# LCDTFT_FPC50P_RGB.net
KiCad netlist of a schematic drawn in Altium Designer
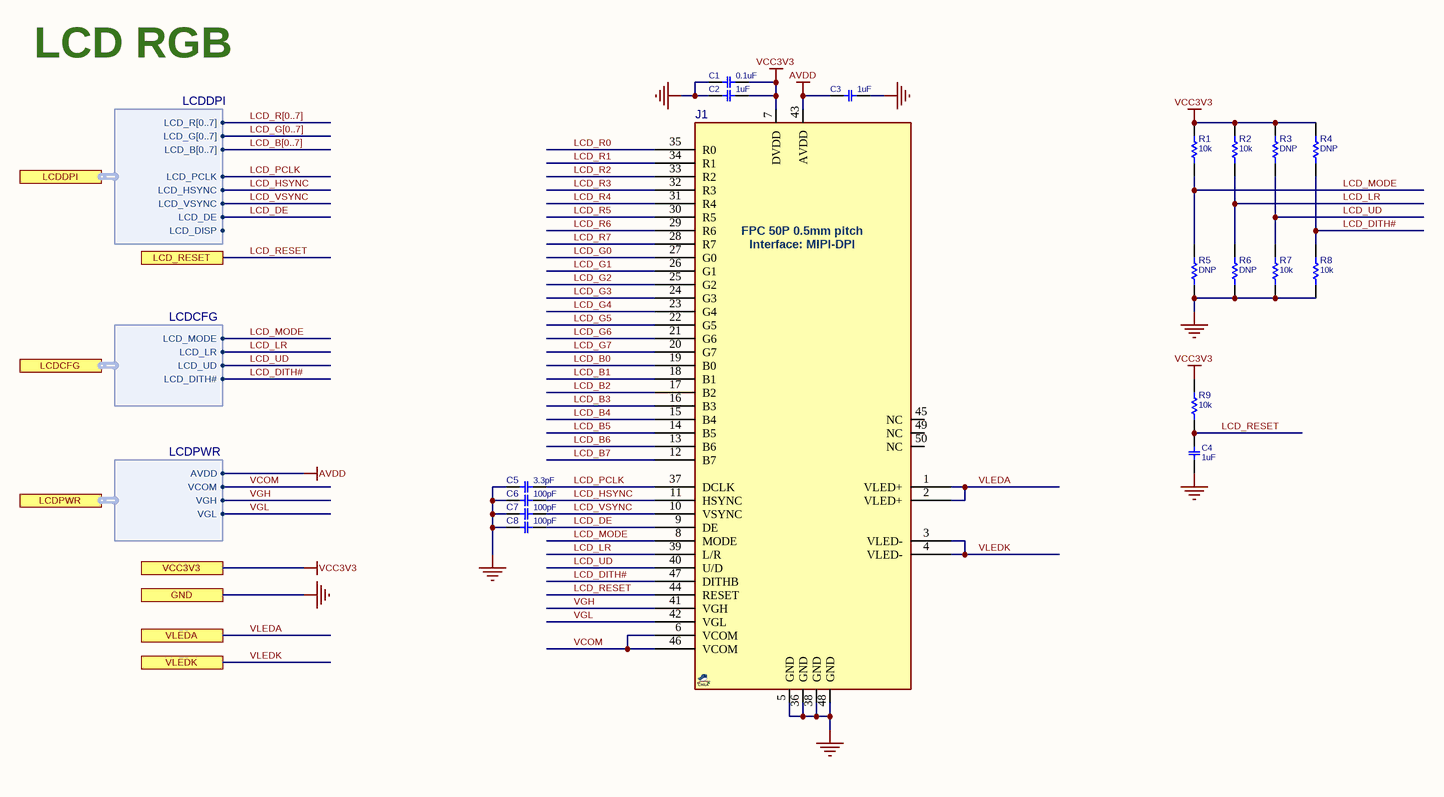
[diagram p0: LCDTFT_FPC50P_RGB.SchDoc]

(export (version "E")
  (design (tool "Eeschema 10.0.6"))
  (components
    (comp (ref "C1")
      (value "0.1uF")
      (footprint "C0402")
      (description "CAP, MLCC")
      (fields (field (name "MANF_P#") "GRM155R71H104KE14D") (field (name "MANF") "Murata"))
      (libsource (lib "passive_smd") (part "CAP_SMD_MLCC"))
    )
    (comp (ref "C2")
      (value "1uF")
      (footprint "C0402")
      (description "CAP, MLCC")
      (fields (field (name "MANF_P#") "CL05A105KO5NNND") (field (name "MANF") "Samsung"))
      (libsource (lib "passive_smd") (part "CAP_SMD_MLCC"))
    )
    (comp (ref "C3")
      (value "1uF")
      (footprint "C0402")
      (description "CAP, MLCC")
      (fields (field (name "MANF_P#") "CL05A105KO5NNND") (field (name "MANF") "Samsung"))
      (libsource (lib "passive_smd") (part "CAP_SMD_MLCC"))
    )
    (comp (ref "C4")
      (value "1uF")
      (footprint "C0402")
      (description "CAP, MLCC")
      (fields (field (name "MANF_P#") "CL05A105KO5NNND") (field (name "MANF") "Samsung"))
      (libsource (lib "passive_smd") (part "CAP_SMD_MLCC"))
    )
    (comp (ref "C5")
      (value "3.3pF")
      (footprint "C0402")
      (description "CAP, MLCC")
      (libsource (lib "passive_smd") (part "CAP_SMD_MLCC"))
    )
    (comp (ref "C6")
      (value "100pF")
      (footprint "C0402")
      (description "CAP, MLCC")
      (libsource (lib "passive_smd") (part "CAP_SMD_MLCC"))
    )
    (comp (ref "C7")
      (value "100pF")
      (footprint "C0402")
      (description "CAP, MLCC")
      (libsource (lib "passive_smd") (part "CAP_SMD_MLCC"))
    )
    (comp (ref "C8")
      (value "100pF")
      (footprint "C0402")
      (description "CAP, MLCC")
      (libsource (lib "passive_smd") (part "CAP_SMD_MLCC"))
    )
    (comp (ref "J1")
      (value "FPC_50_0.5mm")
      (footprint "FPC50_50D_FFC2B29")
      (description "LCD TFT Color, FPC50P, RGB")
      (libsource (lib "lcdtft") (part "LCDTFT_DPI_FPC50P"))
    )
    (comp (ref "R1")
      (value "10k")
      (footprint "R0402")
      (description "RESISTOR, SMD")
      (libsource (lib "passive_res_smd") (part "RES_SMD"))
    )
    (comp (ref "R2")
      (value "10k")
      (footprint "R0402")
      (description "RESISTOR, SMD")
      (libsource (lib "passive_res_smd") (part "RES_SMD"))
    )
    (comp (ref "R3")
      (value "DNP")
      (footprint "R0402")
      (description "RESISTOR, SMD")
      (libsource (lib "passive_res_smd") (part "RES_SMD"))
    )
    (comp (ref "R4")
      (value "DNP")
      (footprint "R0402")
      (description "RESISTOR, SMD")
      (libsource (lib "passive_res_smd") (part "RES_SMD"))
    )
    (comp (ref "R5")
      (value "DNP")
      (footprint "R0402")
      (description "RESISTOR, SMD")
      (libsource (lib "passive_res_smd") (part "RES_SMD"))
    )
    (comp (ref "R6")
      (value "DNP")
      (footprint "R0402")
      (description "RESISTOR, SMD")
      (libsource (lib "passive_res_smd") (part "RES_SMD"))
    )
    (comp (ref "R7")
      (value "10k")
      (footprint "R0402")
      (description "RESISTOR, SMD")
      (libsource (lib "passive_res_smd") (part "RES_SMD"))
    )
    (comp (ref "R8")
      (value "10k")
      (footprint "R0402")
      (description "RESISTOR, SMD")
      (libsource (lib "passive_res_smd") (part "RES_SMD"))
    )
    (comp (ref "R9")
      (value "10k")
      (footprint "R0402")
      (description "RESISTOR, SMD")
      (libsource (lib "passive_res_smd") (part "RES_SMD"))
    )
  )
  (nets
    (net (code "4") (name "/LCD_B0") (class "Default")
      (node (ref "J1") (pin "19") (pinfunction "B0_19") (pintype "passive"))
    )
    (net (code "5") (name "/LCD_B1") (class "Default")
      (node (ref "J1") (pin "18") (pinfunction "B1_18") (pintype "passive"))
    )
    (net (code "6") (name "/LCD_B2") (class "Default")
      (node (ref "J1") (pin "17") (pinfunction "B2_17") (pintype "passive"))
    )
    (net (code "7") (name "/LCD_B3") (class "Default")
      (node (ref "J1") (pin "16") (pinfunction "B3_16") (pintype "passive"))
    )
    (net (code "8") (name "/LCD_B4") (class "Default")
      (node (ref "J1") (pin "15") (pinfunction "B4_15") (pintype "passive"))
    )
    (net (code "9") (name "/LCD_B5") (class "Default")
      (node (ref "J1") (pin "14") (pinfunction "B5_14") (pintype "passive"))
    )
    (net (code "10") (name "/LCD_B6") (class "Default")
      (node (ref "J1") (pin "13") (pinfunction "B6_13") (pintype "passive"))
    )
    (net (code "11") (name "/LCD_B7") (class "Default")
      (node (ref "J1") (pin "12") (pinfunction "B7_12") (pintype "passive"))
    )
    (net (code "13") (name "/LCD_DE") (class "Default")
      (node (ref "C8") (pin "1") (pinfunction "1_1") (pintype "passive"))
      (node (ref "J1") (pin "9") (pinfunction "DE_9") (pintype "passive"))
    )
    (net (code "14") (name "/LCD_DITH#") (class "Default")
      (node (ref "J1") (pin "47") (pinfunction "DITHB_47") (pintype "passive"))
      (node (ref "R4") (pin "2") (pinfunction "2_2") (pintype "passive"))
      (node (ref "R8") (pin "1") (pinfunction "1_1") (pintype "passive"))
    )
    (net (code "15") (name "/LCD_G0") (class "Default")
      (node (ref "J1") (pin "27") (pinfunction "G0_27") (pintype "passive"))
    )
    (net (code "16") (name "/LCD_G1") (class "Default")
      (node (ref "J1") (pin "26") (pinfunction "G1_26") (pintype "passive"))
    )
    (net (code "17") (name "/LCD_G2") (class "Default")
      (node (ref "J1") (pin "25") (pinfunction "G2_25") (pintype "passive"))
    )
    (net (code "18") (name "/LCD_G3") (class "Default")
      (node (ref "J1") (pin "24") (pinfunction "G3_24") (pintype "passive"))
    )
    (net (code "19") (name "/LCD_G4") (class "Default")
      (node (ref "J1") (pin "23") (pinfunction "G4_23") (pintype "passive"))
    )
    (net (code "20") (name "/LCD_G5") (class "Default")
      (node (ref "J1") (pin "22") (pinfunction "G5_22") (pintype "passive"))
    )
    (net (code "21") (name "/LCD_G6") (class "Default")
      (node (ref "J1") (pin "21") (pinfunction "G6_21") (pintype "passive"))
    )
    (net (code "22") (name "/LCD_G7") (class "Default")
      (node (ref "J1") (pin "20") (pinfunction "G7_20") (pintype "passive"))
    )
    (net (code "24") (name "/LCD_HSYNC") (class "Default")
      (node (ref "C6") (pin "1") (pinfunction "1_1") (pintype "passive"))
      (node (ref "J1") (pin "11") (pinfunction "HSYNC_11") (pintype "passive"))
    )
    (net (code "25") (name "/LCD_LR") (class "Default")
      (node (ref "J1") (pin "39") (pinfunction "L/R_39") (pintype "passive"))
      (node (ref "R2") (pin "2") (pinfunction "2_2") (pintype "passive"))
      (node (ref "R6") (pin "1") (pinfunction "1_1") (pintype "passive"))
    )
    (net (code "26") (name "/LCD_MODE") (class "Default")
      (node (ref "J1") (pin "8") (pinfunction "MODE_8") (pintype "passive"))
      (node (ref "R1") (pin "2") (pinfunction "2_2") (pintype "passive"))
      (node (ref "R5") (pin "1") (pinfunction "1_1") (pintype "passive"))
    )
    (net (code "27") (name "/LCD_PCLK") (class "Default")
      (node (ref "C5") (pin "1") (pinfunction "1_1") (pintype "passive"))
      (node (ref "J1") (pin "37") (pinfunction "DCLK_37") (pintype "passive"))
    )
    (net (code "28") (name "/LCD_R0") (class "Default")
      (node (ref "J1") (pin "35") (pinfunction "R0_35") (pintype "passive"))
    )
    (net (code "29") (name "/LCD_R1") (class "Default")
      (node (ref "J1") (pin "34") (pinfunction "R1_34") (pintype "passive"))
    )
    (net (code "30") (name "/LCD_R2") (class "Default")
      (node (ref "J1") (pin "33") (pinfunction "R2_33") (pintype "passive"))
    )
    (net (code "31") (name "/LCD_R3") (class "Default")
      (node (ref "J1") (pin "32") (pinfunction "R3_32") (pintype "passive"))
    )
    (net (code "32") (name "/LCD_R4") (class "Default")
      (node (ref "J1") (pin "31") (pinfunction "R4_31") (pintype "passive"))
    )
    (net (code "33") (name "/LCD_R5") (class "Default")
      (node (ref "J1") (pin "30") (pinfunction "R5_30") (pintype "passive"))
    )
    (net (code "34") (name "/LCD_R6") (class "Default")
      (node (ref "J1") (pin "29") (pinfunction "R6_29") (pintype "passive"))
    )
    (net (code "35") (name "/LCD_R7") (class "Default")
      (node (ref "J1") (pin "28") (pinfunction "R7_28") (pintype "passive"))
    )
    (net (code "36") (name "/LCD_RESET") (class "Default")
      (node (ref "C4") (pin "1") (pinfunction "1_1") (pintype "passive"))
      (node (ref "J1") (pin "44") (pinfunction "RESET_44") (pintype "passive"))
      (node (ref "R9") (pin "2") (pinfunction "2_2") (pintype "passive"))
    )
    (net (code "38") (name "/LCD_UD") (class "Default")
      (node (ref "J1") (pin "40") (pinfunction "U/D_40") (pintype "passive"))
      (node (ref "R3") (pin "2") (pinfunction "2_2") (pintype "passive"))
      (node (ref "R7") (pin "1") (pinfunction "1_1") (pintype "passive"))
    )
    (net (code "39") (name "/LCD_VSYNC") (class "Default")
      (node (ref "C7") (pin "1") (pinfunction "1_1") (pintype "passive"))
      (node (ref "J1") (pin "10") (pinfunction "VSYNC_10") (pintype "passive"))
    )
    (net (code "40") (name "/VCOM") (class "Default")
      (node (ref "J1") (pin "46") (pinfunction "VCOM_46") (pintype "passive"))
      (node (ref "J1") (pin "6") (pinfunction "VCOM_6") (pintype "passive"))
    )
    (net (code "41") (name "/VGH") (class "Default")
      (node (ref "J1") (pin "41") (pinfunction "VGH_41") (pintype "passive"))
    )
    (net (code "42") (name "/VGL") (class "Default")
      (node (ref "J1") (pin "42") (pinfunction "VGL_42") (pintype "passive"))
    )
    (net (code "43") (name "/VLEDA") (class "Default")
      (node (ref "J1") (pin "1") (pinfunction "VLED+_1") (pintype "passive"))
      (node (ref "J1") (pin "2") (pinfunction "VLED+_2") (pintype "passive"))
    )
    (net (code "44") (name "/VLEDK") (class "Default")
      (node (ref "J1") (pin "3") (pinfunction "VLED-_3") (pintype "passive"))
      (node (ref "J1") (pin "4") (pinfunction "VLED-_4") (pintype "passive"))
    )
    (net (code "48") (name "AVDD") (class "Default")
      (node (ref "C3") (pin "2") (pinfunction "2_2") (pintype "passive"))
      (node (ref "J1") (pin "43") (pinfunction "AVDD_43") (pintype "passive"))
    )
    (net (code "49") (name "GND") (class "Default")
      (node (ref "C1") (pin "2") (pinfunction "2_2") (pintype "passive"))
      (node (ref "C2") (pin "2") (pinfunction "2_2") (pintype "passive"))
      (node (ref "C3") (pin "1") (pinfunction "1_1") (pintype "passive"))
      (node (ref "C4") (pin "2") (pinfunction "2_2") (pintype "passive"))
      (node (ref "C5") (pin "2") (pinfunction "2_2") (pintype "passive"))
      (node (ref "C6") (pin "2") (pinfunction "2_2") (pintype "passive"))
      (node (ref "C7") (pin "2") (pinfunction "2_2") (pintype "passive"))
      (node (ref "C8") (pin "2") (pinfunction "2_2") (pintype "passive"))
      (node (ref "J1") (pin "36") (pinfunction "GND_36") (pintype "passive"))
      (node (ref "J1") (pin "38") (pinfunction "GND_38") (pintype "passive"))
      (node (ref "J1") (pin "48") (pinfunction "GND_48") (pintype "passive"))
      (node (ref "J1") (pin "5") (pinfunction "GND_5") (pintype "passive"))
      (node (ref "R5") (pin "2") (pinfunction "2_2") (pintype "passive"))
      (node (ref "R6") (pin "2") (pinfunction "2_2") (pintype "passive"))
      (node (ref "R7") (pin "2") (pinfunction "2_2") (pintype "passive"))
      (node (ref "R8") (pin "2") (pinfunction "2_2") (pintype "passive"))
    )
    (net (code "50") (name "VCC3V3") (class "Default")
      (node (ref "C1") (pin "1") (pinfunction "1_1") (pintype "passive"))
      (node (ref "C2") (pin "1") (pinfunction "1_1") (pintype "passive"))
      (node (ref "J1") (pin "7") (pinfunction "DVDD_7") (pintype "passive"))
      (node (ref "R1") (pin "1") (pinfunction "1_1") (pintype "passive"))
      (node (ref "R2") (pin "1") (pinfunction "1_1") (pintype "passive"))
      (node (ref "R3") (pin "1") (pinfunction "1_1") (pintype "passive"))
      (node (ref "R4") (pin "1") (pinfunction "1_1") (pintype "passive"))
      (node (ref "R9") (pin "1") (pinfunction "1_1") (pintype "passive"))
    )
    (net (code "51") (name "unconnected-(J1-NC-Pad45)") (class "Default")
      (node (ref "J1") (pin "45") (pinfunction "NC_45") (pintype "passive"))
    )
    (net (code "52") (name "unconnected-(J1-NC-Pad49)") (class "Default")
      (node (ref "J1") (pin "49") (pinfunction "NC_49") (pintype "passive"))
    )
    (net (code "53") (name "unconnected-(J1-NC-Pad50)") (class "Default")
      (node (ref "J1") (pin "50") (pinfunction "NC_50") (pintype "passive"))
    )
  )
)
